# schematic.net
KiCad netlist of a schematic drawn in EasyEDA
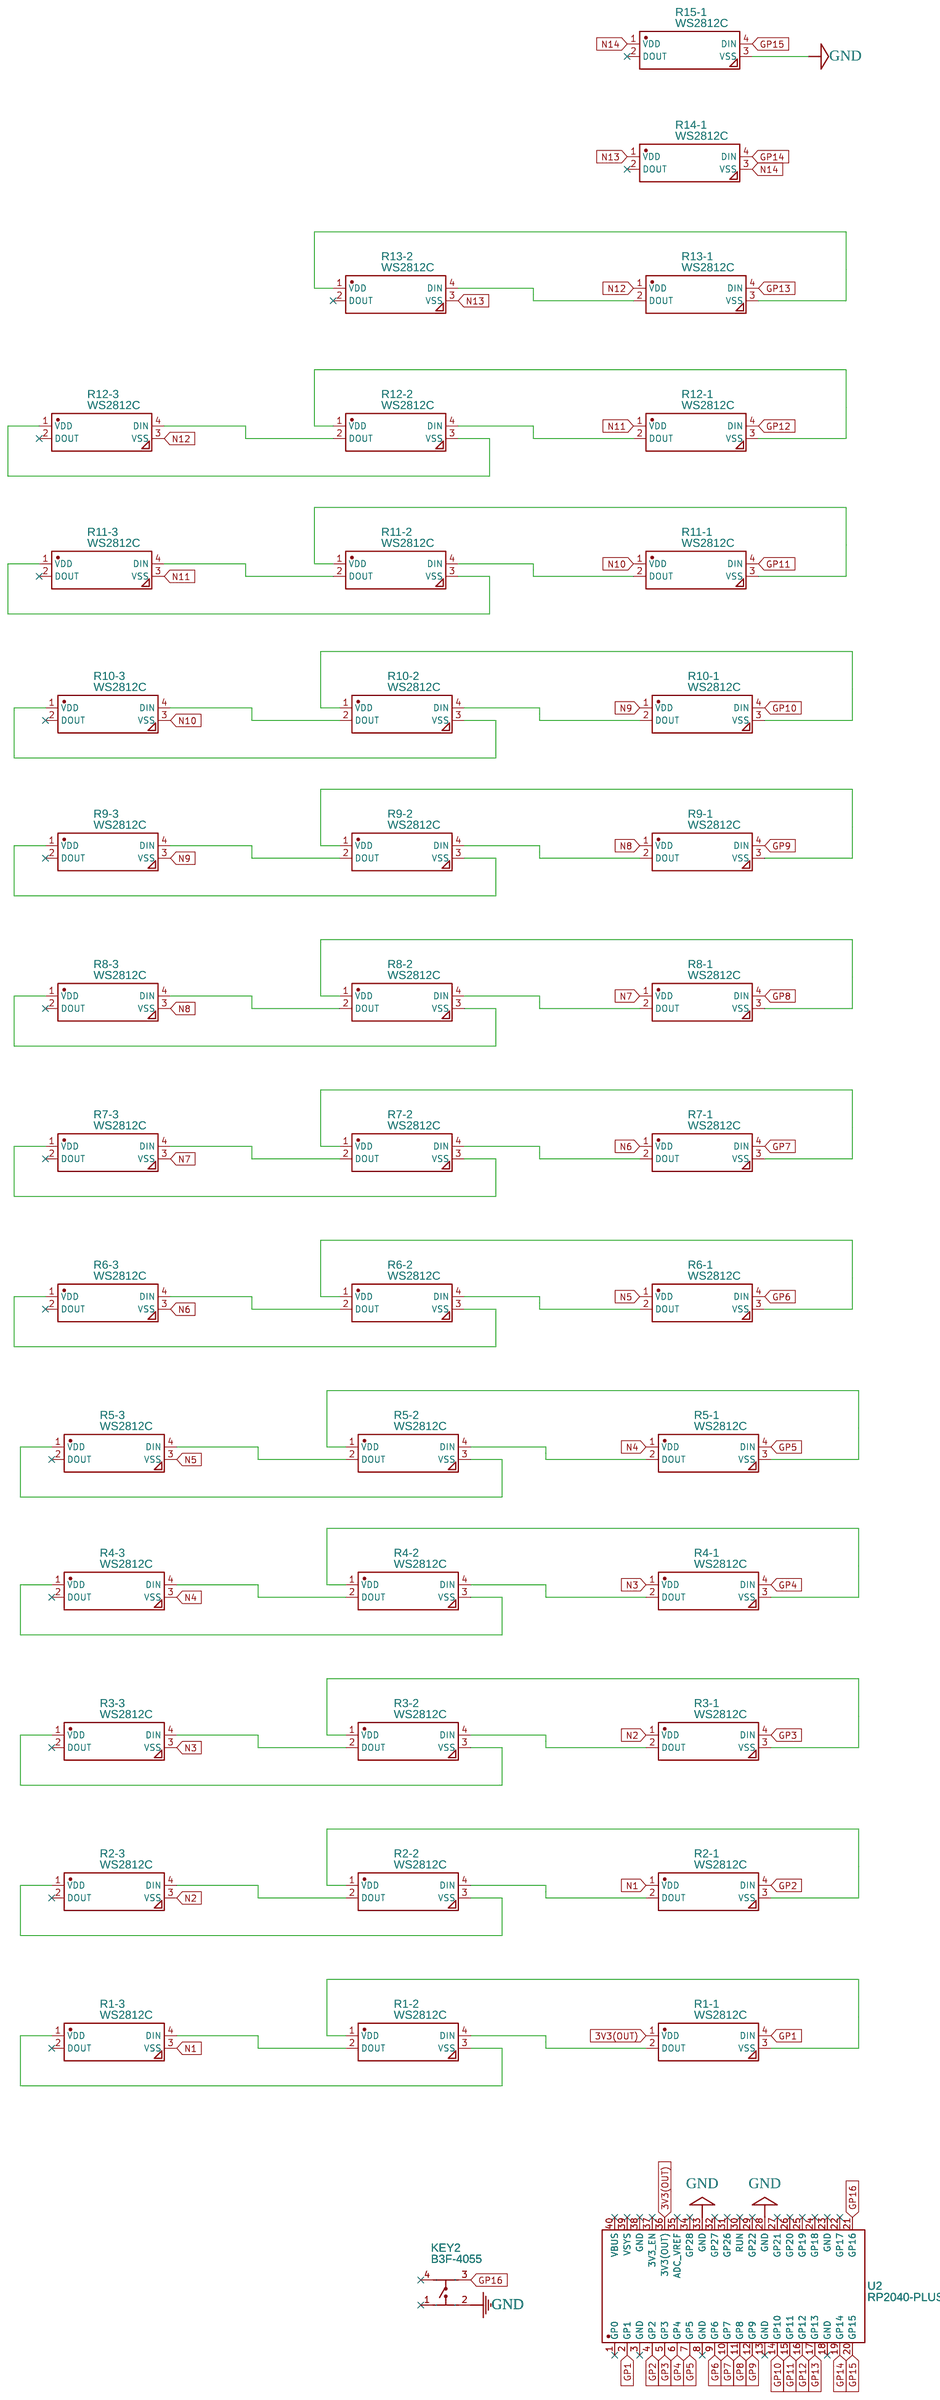
[diagram p0: Sheet_1]
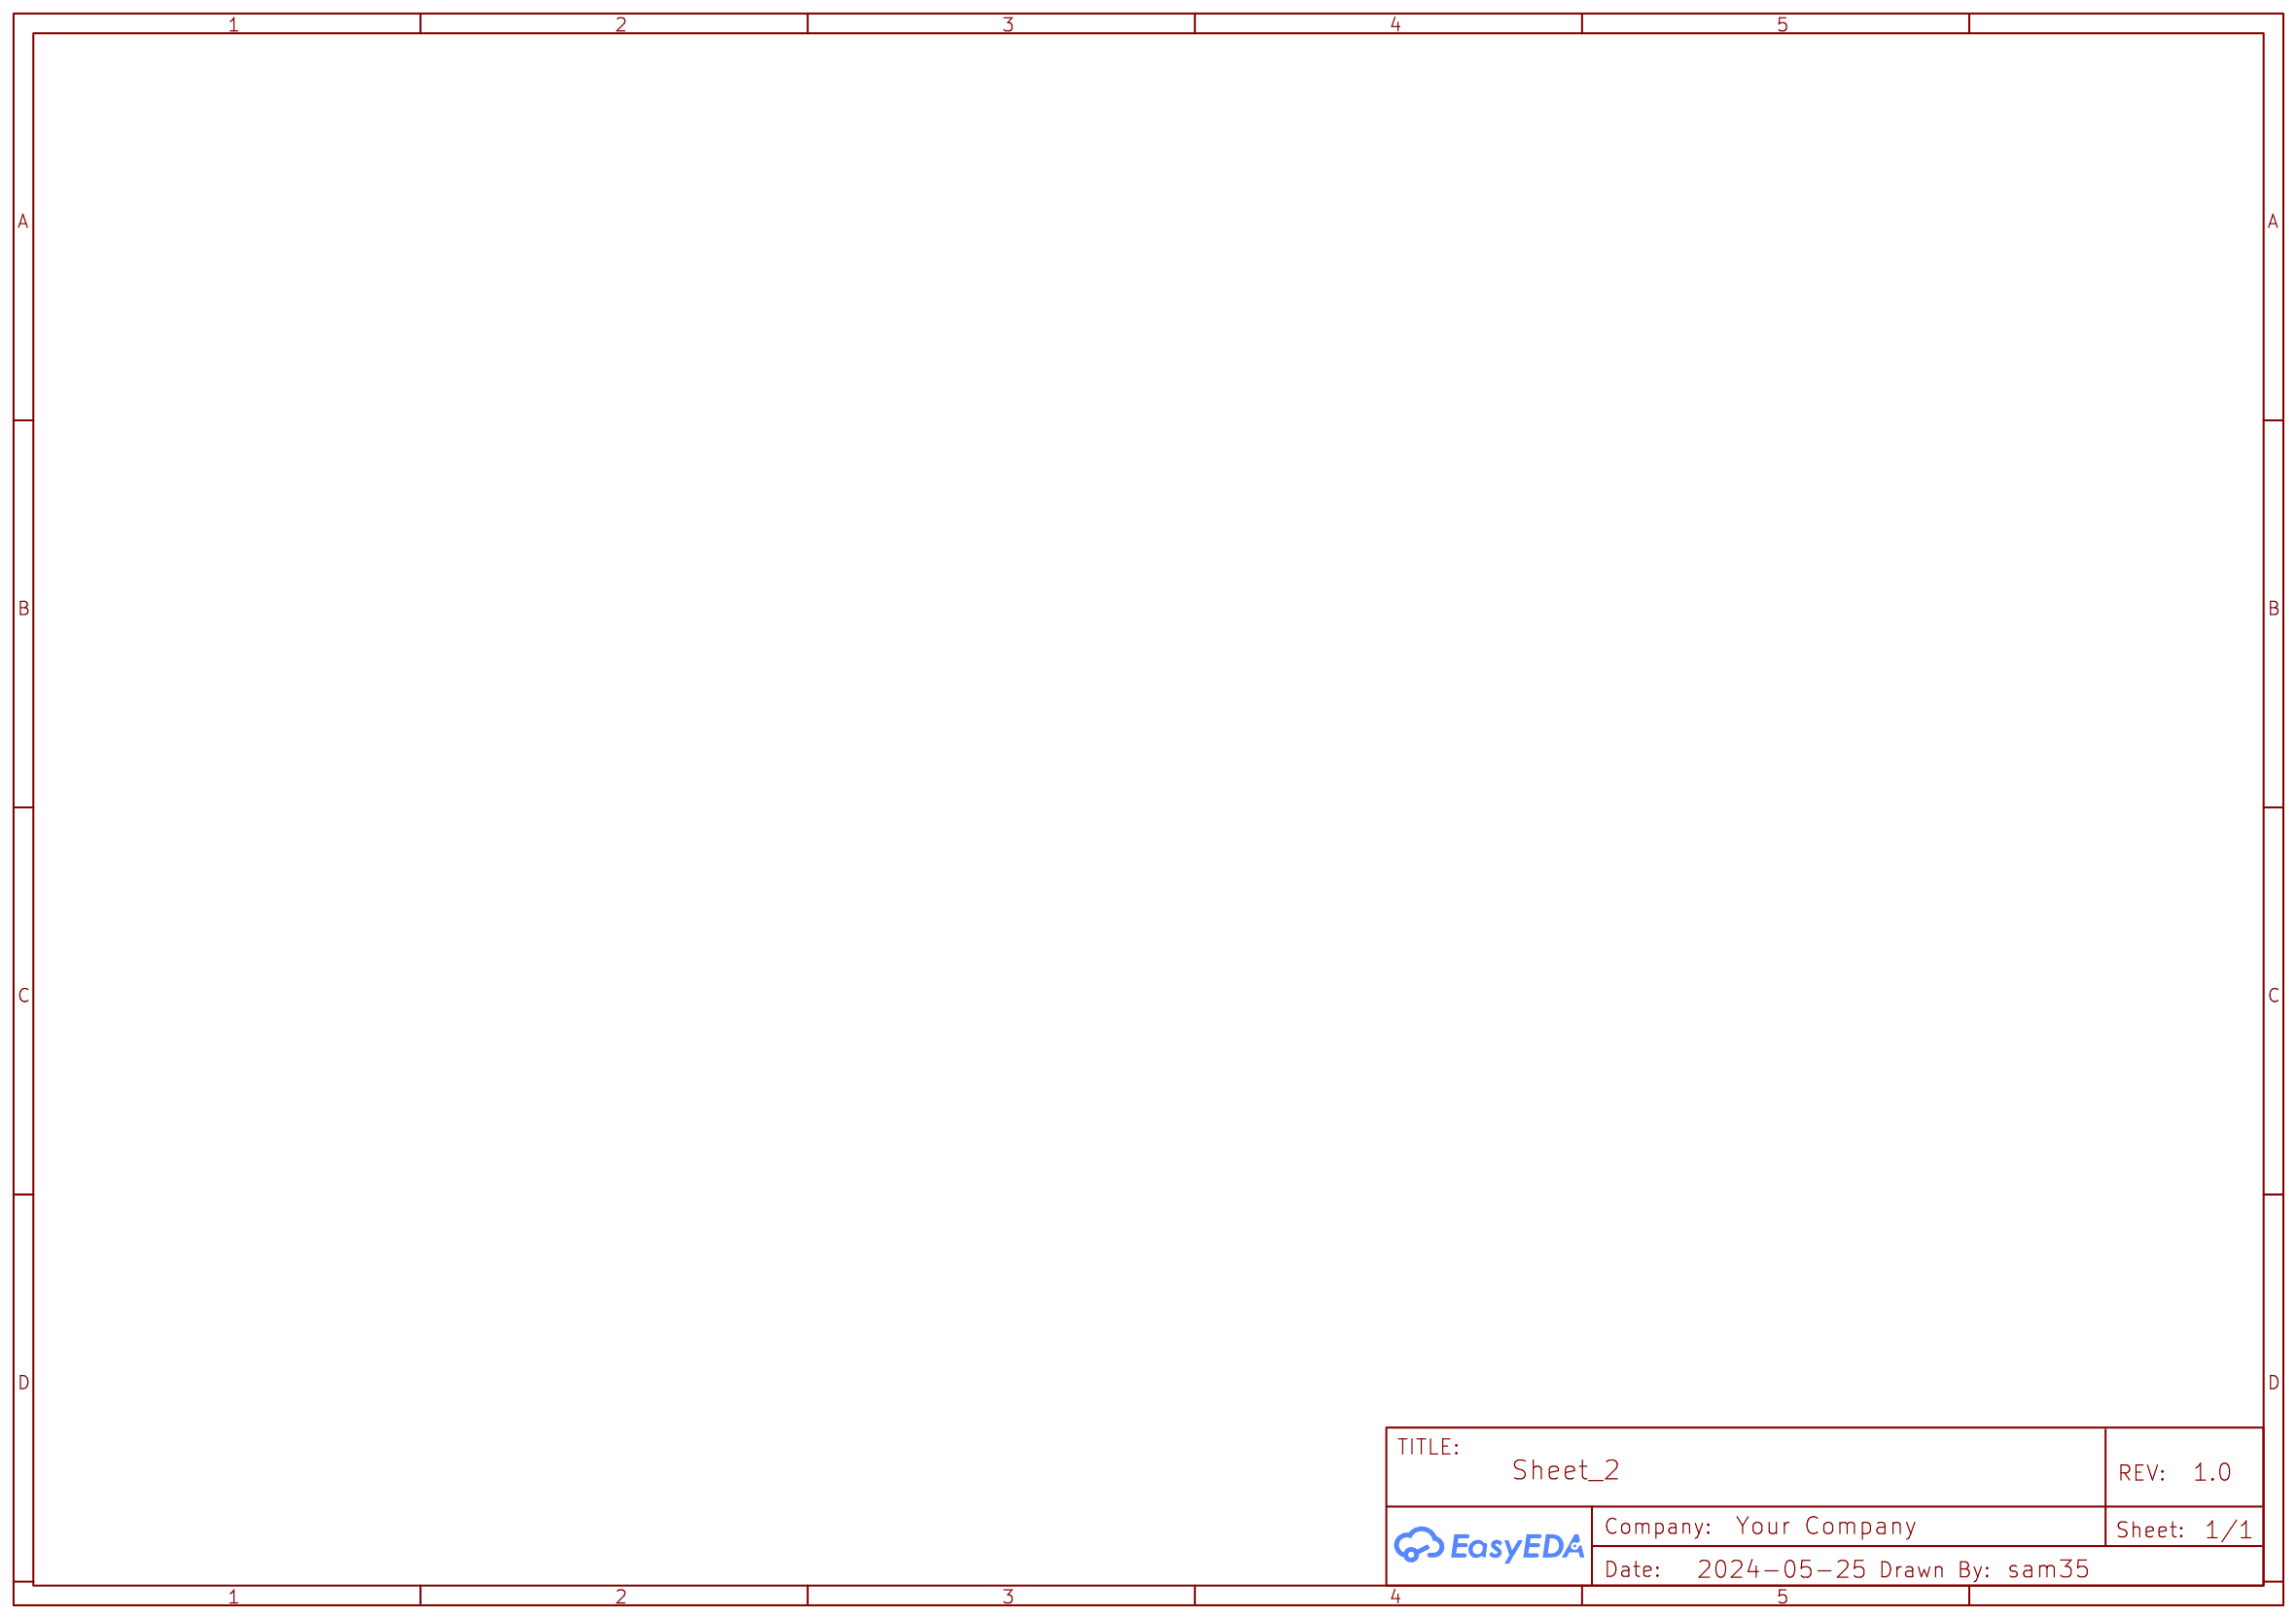
[diagram p1: Sheet_2]

(export (version "E")
  (design (tool "Eeschema 10.0.6"))
  (components
    (comp (ref "KEY2")
      (value "B3F-4055")
      (fields (field (name "Manufacturer") "OMRON(欧姆龙)"))
      (libsource (lib "") (part "B3F-4055"))
    )
    (comp (ref "R1-1")
      (value "WS2812C")
      (fields (field (name "Manufacturer") "worldsemi"))
      (libsource (lib "") (part "WS2812C_10"))
    )
    (comp (ref "R1-2")
      (value "WS2812C")
      (fields (field (name "Manufacturer") "worldsemi"))
      (libsource (lib "") (part "WS2812C_10"))
    )
    (comp (ref "R1-3")
      (value "WS2812C")
      (fields (field (name "Manufacturer") "worldsemi"))
      (libsource (lib "") (part "WS2812C_10"))
    )
    (comp (ref "R2-1")
      (value "WS2812C")
      (fields (field (name "Manufacturer") "worldsemi"))
      (libsource (lib "") (part "WS2812C"))
    )
    (comp (ref "R2-2")
      (value "WS2812C")
      (fields (field (name "Manufacturer") "worldsemi"))
      (libsource (lib "") (part "WS2812C"))
    )
    (comp (ref "R2-3")
      (value "WS2812C")
      (fields (field (name "Manufacturer") "worldsemi"))
      (libsource (lib "") (part "WS2812C"))
    )
    (comp (ref "R3-1")
      (value "WS2812C")
      (fields (field (name "Manufacturer") "worldsemi"))
      (libsource (lib "") (part "WS2812C_11"))
    )
    (comp (ref "R3-2")
      (value "WS2812C")
      (fields (field (name "Manufacturer") "worldsemi"))
      (libsource (lib "") (part "WS2812C_11"))
    )
    (comp (ref "R3-3")
      (value "WS2812C")
      (fields (field (name "Manufacturer") "worldsemi"))
      (libsource (lib "") (part "WS2812C_11"))
    )
    (comp (ref "R4-1")
      (value "WS2812C")
      (fields (field (name "Manufacturer") "worldsemi"))
      (libsource (lib "") (part "WS2812C_12"))
    )
    (comp (ref "R4-2")
      (value "WS2812C")
      (fields (field (name "Manufacturer") "worldsemi"))
      (libsource (lib "") (part "WS2812C_12"))
    )
    (comp (ref "R4-3")
      (value "WS2812C")
      (fields (field (name "Manufacturer") "worldsemi"))
      (libsource (lib "") (part "WS2812C_12"))
    )
    (comp (ref "R5-1")
      (value "WS2812C")
      (fields (field (name "Manufacturer") "worldsemi"))
      (libsource (lib "") (part "WS2812C_2"))
    )
    (comp (ref "R5-2")
      (value "WS2812C")
      (fields (field (name "Manufacturer") "worldsemi"))
      (libsource (lib "") (part "WS2812C_2"))
    )
    (comp (ref "R5-3")
      (value "WS2812C")
      (fields (field (name "Manufacturer") "worldsemi"))
      (libsource (lib "") (part "WS2812C_2"))
    )
    (comp (ref "R6-1")
      (value "WS2812C")
      (fields (field (name "Manufacturer") "worldsemi"))
      (libsource (lib "") (part "WS2812C_3"))
    )
    (comp (ref "R6-2")
      (value "WS2812C")
      (fields (field (name "Manufacturer") "worldsemi"))
      (libsource (lib "") (part "WS2812C_3"))
    )
    (comp (ref "R6-3")
      (value "WS2812C")
      (fields (field (name "Manufacturer") "worldsemi"))
      (libsource (lib "") (part "WS2812C_3"))
    )
    (comp (ref "R7-1")
      (value "WS2812C")
      (fields (field (name "Manufacturer") "worldsemi"))
      (libsource (lib "") (part "WS2812C_13"))
    )
    (comp (ref "R7-2")
      (value "WS2812C")
      (fields (field (name "Manufacturer") "worldsemi"))
      (libsource (lib "") (part "WS2812C_13"))
    )
    (comp (ref "R7-3")
      (value "WS2812C")
      (fields (field (name "Manufacturer") "worldsemi"))
      (libsource (lib "") (part "WS2812C_13"))
    )
    (comp (ref "R8-1")
      (value "WS2812C")
      (fields (field (name "Manufacturer") "worldsemi"))
      (libsource (lib "") (part "WS2812C_5"))
    )
    (comp (ref "R8-2")
      (value "WS2812C")
      (fields (field (name "Manufacturer") "worldsemi"))
      (libsource (lib "") (part "WS2812C_5"))
    )
    (comp (ref "R8-3")
      (value "WS2812C")
      (fields (field (name "Manufacturer") "worldsemi"))
      (libsource (lib "") (part "WS2812C_5"))
    )
    (comp (ref "R9-1")
      (value "WS2812C")
      (fields (field (name "Manufacturer") "worldsemi"))
      (libsource (lib "") (part "WS2812C_1"))
    )
    (comp (ref "R9-2")
      (value "WS2812C")
      (fields (field (name "Manufacturer") "worldsemi"))
      (libsource (lib "") (part "WS2812C_1"))
    )
    (comp (ref "R9-3")
      (value "WS2812C")
      (fields (field (name "Manufacturer") "worldsemi"))
      (libsource (lib "") (part "WS2812C_1"))
    )
    (comp (ref "R10-1")
      (value "WS2812C")
      (fields (field (name "Manufacturer") "worldsemi"))
      (libsource (lib "") (part "WS2812C_9"))
    )
    (comp (ref "R10-2")
      (value "WS2812C")
      (fields (field (name "Manufacturer") "worldsemi"))
      (libsource (lib "") (part "WS2812C_9"))
    )
    (comp (ref "R10-3")
      (value "WS2812C")
      (fields (field (name "Manufacturer") "worldsemi"))
      (libsource (lib "") (part "WS2812C_9"))
    )
    (comp (ref "R11-1")
      (value "WS2812C")
      (fields (field (name "Manufacturer") "worldsemi"))
      (libsource (lib "") (part "WS2812C_7"))
    )
    (comp (ref "R11-2")
      (value "WS2812C")
      (fields (field (name "Manufacturer") "worldsemi"))
      (libsource (lib "") (part "WS2812C_7"))
    )
    (comp (ref "R11-3")
      (value "WS2812C")
      (fields (field (name "Manufacturer") "worldsemi"))
      (libsource (lib "") (part "WS2812C_7"))
    )
    (comp (ref "R12-1")
      (value "WS2812C")
      (fields (field (name "Manufacturer") "worldsemi"))
      (libsource (lib "") (part "WS2812C_8"))
    )
    (comp (ref "R12-2")
      (value "WS2812C")
      (fields (field (name "Manufacturer") "worldsemi"))
      (libsource (lib "") (part "WS2812C_8"))
    )
    (comp (ref "R12-3")
      (value "WS2812C")
      (fields (field (name "Manufacturer") "worldsemi"))
      (libsource (lib "") (part "WS2812C_8"))
    )
    (comp (ref "R13-1")
      (value "WS2812C")
      (fields (field (name "Manufacturer") "worldsemi"))
      (libsource (lib "") (part "WS2812C_4"))
    )
    (comp (ref "R13-2")
      (value "WS2812C")
      (fields (field (name "Manufacturer") "worldsemi"))
      (libsource (lib "") (part "WS2812C_4"))
    )
    (comp (ref "R14-1")
      (value "WS2812C")
      (fields (field (name "Manufacturer") "worldsemi"))
      (libsource (lib "") (part "WS2812C_6"))
    )
    (comp (ref "R15-1")
      (value "WS2812C")
      (fields (field (name "Manufacturer") "worldsemi"))
      (libsource (lib "") (part "WS2812C_14"))
    )
    (comp (ref "U2")
      (value "RP2040-PLUS")
      (fields
        (field (name "Manufacturer Part") "RP2040-Plus")
        (field (name "Manufacturer") "Waveshare(微雪电子)")
      )
      (libsource (lib "") (part "RP2040-PLUS"))
    )
  )
  (nets
    (net (code "1") (name "3V3(OUT)") (class "Default")
      (node (ref "R1-1") (pin "1") (pinfunction "VDD_1") (pintype "unspecified"))
      (node (ref "U2") (pin "36") (pinfunction "3V3(OUT)_36") (pintype "unspecified"))
    )
    (net (code "2") (name "GND") (class "Default")
      (node (ref "KEY2") (pin "2") (pinfunction "2_2") (pintype "unspecified"))
      (node (ref "R15-1") (pin "3") (pinfunction "VSS_3") (pintype "unspecified"))
      (node (ref "U2") (pin "28") (pinfunction "GND_28") (pintype "unspecified"))
      (node (ref "U2") (pin "33") (pinfunction "GND_33") (pintype "unspecified"))
    )
    (net (code "3") (name "GP1") (class "Default")
      (node (ref "R1-1") (pin "4") (pinfunction "DIN_4") (pintype "unspecified"))
      (node (ref "U2") (pin "2") (pinfunction "GP1_2") (pintype "unspecified"))
    )
    (net (code "4") (name "GP2") (class "Default")
      (node (ref "R2-1") (pin "4") (pinfunction "DIN_4") (pintype "unspecified"))
      (node (ref "U2") (pin "4") (pinfunction "GP2_4") (pintype "unspecified"))
    )
    (net (code "5") (name "GP3") (class "Default")
      (node (ref "R3-1") (pin "4") (pinfunction "DIN_4") (pintype "unspecified"))
      (node (ref "U2") (pin "5") (pinfunction "GP3_5") (pintype "unspecified"))
    )
    (net (code "6") (name "GP4") (class "Default")
      (node (ref "R4-1") (pin "4") (pinfunction "DIN_4") (pintype "unspecified"))
      (node (ref "U2") (pin "6") (pinfunction "GP4_6") (pintype "unspecified"))
    )
    (net (code "7") (name "GP5") (class "Default")
      (node (ref "R5-1") (pin "4") (pinfunction "DIN_4") (pintype "unspecified"))
      (node (ref "U2") (pin "7") (pinfunction "GP5_7") (pintype "unspecified"))
    )
    (net (code "8") (name "GP6") (class "Default")
      (node (ref "R6-1") (pin "4") (pinfunction "DIN_4") (pintype "unspecified"))
      (node (ref "U2") (pin "9") (pinfunction "GP6_9") (pintype "unspecified"))
    )
    (net (code "9") (name "GP7") (class "Default")
      (node (ref "R7-1") (pin "4") (pinfunction "DIN_4") (pintype "unspecified"))
      (node (ref "U2") (pin "10") (pinfunction "GP7_10") (pintype "unspecified"))
    )
    (net (code "10") (name "GP8") (class "Default")
      (node (ref "R8-1") (pin "4") (pinfunction "DIN_4") (pintype "unspecified"))
      (node (ref "U2") (pin "11") (pinfunction "GP8_11") (pintype "unspecified"))
    )
    (net (code "11") (name "GP9") (class "Default")
      (node (ref "R9-1") (pin "4") (pinfunction "DIN_4") (pintype "unspecified"))
      (node (ref "U2") (pin "12") (pinfunction "GP9_12") (pintype "unspecified"))
    )
    (net (code "12") (name "GP10") (class "Default")
      (node (ref "R10-1") (pin "4") (pinfunction "DIN_4") (pintype "unspecified"))
      (node (ref "U2") (pin "14") (pinfunction "GP10_14") (pintype "unspecified"))
    )
    (net (code "13") (name "GP11") (class "Default")
      (node (ref "R11-1") (pin "4") (pinfunction "DIN_4") (pintype "unspecified"))
      (node (ref "U2") (pin "15") (pinfunction "GP11_15") (pintype "unspecified"))
    )
    (net (code "14") (name "GP12") (class "Default")
      (node (ref "R12-1") (pin "4") (pinfunction "DIN_4") (pintype "unspecified"))
      (node (ref "U2") (pin "16") (pinfunction "GP12_16") (pintype "unspecified"))
    )
    (net (code "15") (name "GP13") (class "Default")
      (node (ref "R13-1") (pin "4") (pinfunction "DIN_4") (pintype "unspecified"))
      (node (ref "U2") (pin "17") (pinfunction "GP13_17") (pintype "unspecified"))
    )
    (net (code "16") (name "GP14") (class "Default")
      (node (ref "R14-1") (pin "4") (pinfunction "DIN_4") (pintype "unspecified"))
      (node (ref "U2") (pin "19") (pinfunction "GP14_19") (pintype "unspecified"))
    )
    (net (code "17") (name "GP15") (class "Default")
      (node (ref "R15-1") (pin "4") (pinfunction "DIN_4") (pintype "unspecified"))
      (node (ref "U2") (pin "20") (pinfunction "GP15_20") (pintype "unspecified"))
    )
    (net (code "18") (name "GP16") (class "Default")
      (node (ref "KEY2") (pin "3") (pinfunction "3_3") (pintype "unspecified"))
      (node (ref "U2") (pin "21") (pinfunction "GP16_21") (pintype "unspecified"))
    )
    (net (code "19") (name "N1") (class "Default")
      (node (ref "R1-3") (pin "3") (pinfunction "VSS_3") (pintype "unspecified"))
      (node (ref "R2-1") (pin "1") (pinfunction "VDD_1") (pintype "unspecified"))
    )
    (net (code "20") (name "N2") (class "Default")
      (node (ref "R2-3") (pin "3") (pinfunction "VSS_3") (pintype "unspecified"))
      (node (ref "R3-1") (pin "1") (pinfunction "VDD_1") (pintype "unspecified"))
    )
    (net (code "21") (name "N3") (class "Default")
      (node (ref "R3-3") (pin "3") (pinfunction "VSS_3") (pintype "unspecified"))
      (node (ref "R4-1") (pin "1") (pinfunction "VDD_1") (pintype "unspecified"))
    )
    (net (code "22") (name "N4") (class "Default")
      (node (ref "R4-3") (pin "3") (pinfunction "VSS_3") (pintype "unspecified"))
      (node (ref "R5-1") (pin "1") (pinfunction "VDD_1") (pintype "unspecified"))
    )
    (net (code "23") (name "N5") (class "Default")
      (node (ref "R5-3") (pin "3") (pinfunction "VSS_3") (pintype "unspecified"))
      (node (ref "R6-1") (pin "1") (pinfunction "VDD_1") (pintype "unspecified"))
    )
    (net (code "24") (name "N6") (class "Default")
      (node (ref "R6-3") (pin "3") (pinfunction "VSS_3") (pintype "unspecified"))
      (node (ref "R7-1") (pin "1") (pinfunction "VDD_1") (pintype "unspecified"))
    )
    (net (code "25") (name "N7") (class "Default")
      (node (ref "R7-3") (pin "3") (pinfunction "VSS_3") (pintype "unspecified"))
      (node (ref "R8-1") (pin "1") (pinfunction "VDD_1") (pintype "unspecified"))
    )
    (net (code "26") (name "N8") (class "Default")
      (node (ref "R8-3") (pin "3") (pinfunction "VSS_3") (pintype "unspecified"))
      (node (ref "R9-1") (pin "1") (pinfunction "VDD_1") (pintype "unspecified"))
    )
    (net (code "27") (name "N9") (class "Default")
      (node (ref "R10-1") (pin "1") (pinfunction "VDD_1") (pintype "unspecified"))
      (node (ref "R9-3") (pin "3") (pinfunction "VSS_3") (pintype "unspecified"))
    )
    (net (code "28") (name "N10") (class "Default")
      (node (ref "R10-3") (pin "3") (pinfunction "VSS_3") (pintype "unspecified"))
      (node (ref "R11-1") (pin "1") (pinfunction "VDD_1") (pintype "unspecified"))
    )
    (net (code "29") (name "N11") (class "Default")
      (node (ref "R11-3") (pin "3") (pinfunction "VSS_3") (pintype "unspecified"))
      (node (ref "R12-1") (pin "1") (pinfunction "VDD_1") (pintype "unspecified"))
    )
    (net (code "30") (name "N12") (class "Default")
      (node (ref "R12-3") (pin "3") (pinfunction "VSS_3") (pintype "unspecified"))
      (node (ref "R13-1") (pin "1") (pinfunction "VDD_1") (pintype "unspecified"))
    )
    (net (code "31") (name "N13") (class "Default")
      (node (ref "R13-2") (pin "3") (pinfunction "VSS_3") (pintype "unspecified"))
      (node (ref "R14-1") (pin "1") (pinfunction "VDD_1") (pintype "unspecified"))
    )
    (net (code "32") (name "N14") (class "Default")
      (node (ref "R14-1") (pin "3") (pinfunction "VSS_3") (pintype "unspecified"))
      (node (ref "R15-1") (pin "1") (pinfunction "VDD_1") (pintype "unspecified"))
    )
    (net (code "33") (name "Net-(R1-1-DOUT)") (class "Default")
      (node (ref "R1-1") (pin "2") (pinfunction "DOUT_2") (pintype "unspecified"))
      (node (ref "R1-2") (pin "4") (pinfunction "DIN_4") (pintype "unspecified"))
    )
    (net (code "34") (name "Net-(R1-1-VSS)") (class "Default")
      (node (ref "R1-1") (pin "3") (pinfunction "VSS_3") (pintype "unspecified"))
      (node (ref "R1-2") (pin "1") (pinfunction "VDD_1") (pintype "unspecified"))
    )
    (net (code "35") (name "Net-(R1-2-DOUT)") (class "Default")
      (node (ref "R1-2") (pin "2") (pinfunction "DOUT_2") (pintype "unspecified"))
      (node (ref "R1-3") (pin "4") (pinfunction "DIN_4") (pintype "unspecified"))
    )
    (net (code "36") (name "Net-(R1-2-VSS)") (class "Default")
      (node (ref "R1-2") (pin "3") (pinfunction "VSS_3") (pintype "unspecified"))
      (node (ref "R1-3") (pin "1") (pinfunction "VDD_1") (pintype "unspecified"))
    )
    (net (code "37") (name "Net-(R2-1-DOUT)") (class "Default")
      (node (ref "R2-1") (pin "2") (pinfunction "DOUT_2") (pintype "unspecified"))
      (node (ref "R2-2") (pin "4") (pinfunction "DIN_4") (pintype "unspecified"))
    )
    (net (code "38") (name "Net-(R2-1-VSS)") (class "Default")
      (node (ref "R2-1") (pin "3") (pinfunction "VSS_3") (pintype "unspecified"))
      (node (ref "R2-2") (pin "1") (pinfunction "VDD_1") (pintype "unspecified"))
    )
    (net (code "39") (name "Net-(R2-2-DOUT)") (class "Default")
      (node (ref "R2-2") (pin "2") (pinfunction "DOUT_2") (pintype "unspecified"))
      (node (ref "R2-3") (pin "4") (pinfunction "DIN_4") (pintype "unspecified"))
    )
    (net (code "40") (name "Net-(R2-2-VSS)") (class "Default")
      (node (ref "R2-2") (pin "3") (pinfunction "VSS_3") (pintype "unspecified"))
      (node (ref "R2-3") (pin "1") (pinfunction "VDD_1") (pintype "unspecified"))
    )
    (net (code "41") (name "Net-(R3-1-DOUT)") (class "Default")
      (node (ref "R3-1") (pin "2") (pinfunction "DOUT_2") (pintype "unspecified"))
      (node (ref "R3-2") (pin "4") (pinfunction "DIN_4") (pintype "unspecified"))
    )
    (net (code "42") (name "Net-(R3-1-VSS)") (class "Default")
      (node (ref "R3-1") (pin "3") (pinfunction "VSS_3") (pintype "unspecified"))
      (node (ref "R3-2") (pin "1") (pinfunction "VDD_1") (pintype "unspecified"))
    )
    (net (code "43") (name "Net-(R3-2-DOUT)") (class "Default")
      (node (ref "R3-2") (pin "2") (pinfunction "DOUT_2") (pintype "unspecified"))
      (node (ref "R3-3") (pin "4") (pinfunction "DIN_4") (pintype "unspecified"))
    )
    (net (code "44") (name "Net-(R3-2-VSS)") (class "Default")
      (node (ref "R3-2") (pin "3") (pinfunction "VSS_3") (pintype "unspecified"))
      (node (ref "R3-3") (pin "1") (pinfunction "VDD_1") (pintype "unspecified"))
    )
    (net (code "45") (name "Net-(R4-1-DOUT)") (class "Default")
      (node (ref "R4-1") (pin "2") (pinfunction "DOUT_2") (pintype "unspecified"))
      (node (ref "R4-2") (pin "4") (pinfunction "DIN_4") (pintype "unspecified"))
    )
    (net (code "46") (name "Net-(R4-1-VSS)") (class "Default")
      (node (ref "R4-1") (pin "3") (pinfunction "VSS_3") (pintype "unspecified"))
      (node (ref "R4-2") (pin "1") (pinfunction "VDD_1") (pintype "unspecified"))
    )
    (net (code "47") (name "Net-(R4-2-DOUT)") (class "Default")
      (node (ref "R4-2") (pin "2") (pinfunction "DOUT_2") (pintype "unspecified"))
      (node (ref "R4-3") (pin "4") (pinfunction "DIN_4") (pintype "unspecified"))
    )
    (net (code "48") (name "Net-(R4-2-VSS)") (class "Default")
      (node (ref "R4-2") (pin "3") (pinfunction "VSS_3") (pintype "unspecified"))
      (node (ref "R4-3") (pin "1") (pinfunction "VDD_1") (pintype "unspecified"))
    )
    (net (code "49") (name "Net-(R5-1-DOUT)") (class "Default")
      (node (ref "R5-1") (pin "2") (pinfunction "DOUT_2") (pintype "unspecified"))
      (node (ref "R5-2") (pin "4") (pinfunction "DIN_4") (pintype "unspecified"))
    )
    (net (code "50") (name "Net-(R5-1-VSS)") (class "Default")
      (node (ref "R5-1") (pin "3") (pinfunction "VSS_3") (pintype "unspecified"))
      (node (ref "R5-2") (pin "1") (pinfunction "VDD_1") (pintype "unspecified"))
    )
    (net (code "51") (name "Net-(R5-2-DOUT)") (class "Default")
      (node (ref "R5-2") (pin "2") (pinfunction "DOUT_2") (pintype "unspecified"))
      (node (ref "R5-3") (pin "4") (pinfunction "DIN_4") (pintype "unspecified"))
    )
    (net (code "52") (name "Net-(R5-2-VSS)") (class "Default")
      (node (ref "R5-2") (pin "3") (pinfunction "VSS_3") (pintype "unspecified"))
      (node (ref "R5-3") (pin "1") (pinfunction "VDD_1") (pintype "unspecified"))
    )
    (net (code "53") (name "Net-(R6-1-DOUT)") (class "Default")
      (node (ref "R6-1") (pin "2") (pinfunction "DOUT_2") (pintype "unspecified"))
      (node (ref "R6-2") (pin "4") (pinfunction "DIN_4") (pintype "unspecified"))
    )
    (net (code "54") (name "Net-(R6-1-VSS)") (class "Default")
      (node (ref "R6-1") (pin "3") (pinfunction "VSS_3") (pintype "unspecified"))
      (node (ref "R6-2") (pin "1") (pinfunction "VDD_1") (pintype "unspecified"))
    )
    (net (code "55") (name "Net-(R6-2-DOUT)") (class "Default")
      (node (ref "R6-2") (pin "2") (pinfunction "DOUT_2") (pintype "unspecified"))
      (node (ref "R6-3") (pin "4") (pinfunction "DIN_4") (pintype "unspecified"))
    )
    (net (code "56") (name "Net-(R6-2-VSS)") (class "Default")
      (node (ref "R6-2") (pin "3") (pinfunction "VSS_3") (pintype "unspecified"))
      (node (ref "R6-3") (pin "1") (pinfunction "VDD_1") (pintype "unspecified"))
    )
    (net (code "57") (name "Net-(R7-1-DOUT)") (class "Default")
      (node (ref "R7-1") (pin "2") (pinfunction "DOUT_2") (pintype "unspecified"))
      (node (ref "R7-2") (pin "4") (pinfunction "DIN_4") (pintype "unspecified"))
    )
    (net (code "58") (name "Net-(R7-1-VSS)") (class "Default")
      (node (ref "R7-1") (pin "3") (pinfunction "VSS_3") (pintype "unspecified"))
      (node (ref "R7-2") (pin "1") (pinfunction "VDD_1") (pintype "unspecified"))
    )
    (net (code "59") (name "Net-(R7-2-DOUT)") (class "Default")
      (node (ref "R7-2") (pin "2") (pinfunction "DOUT_2") (pintype "unspecified"))
      (node (ref "R7-3") (pin "4") (pinfunction "DIN_4") (pintype "unspecified"))
    )
    (net (code "60") (name "Net-(R7-2-VSS)") (class "Default")
      (node (ref "R7-2") (pin "3") (pinfunction "VSS_3") (pintype "unspecified"))
      (node (ref "R7-3") (pin "1") (pinfunction "VDD_1") (pintype "unspecified"))
    )
    (net (code "61") (name "Net-(R8-1-DOUT)") (class "Default")
      (node (ref "R8-1") (pin "2") (pinfunction "DOUT_2") (pintype "unspecified"))
      (node (ref "R8-2") (pin "4") (pinfunction "DIN_4") (pintype "unspecified"))
    )
    (net (code "62") (name "Net-(R8-1-VSS)") (class "Default")
      (node (ref "R8-1") (pin "3") (pinfunction "VSS_3") (pintype "unspecified"))
      (node (ref "R8-2") (pin "1") (pinfunction "VDD_1") (pintype "unspecified"))
    )
    (net (code "63") (name "Net-(R8-2-DOUT)") (class "Default")
      (node (ref "R8-2") (pin "2") (pinfunction "DOUT_2") (pintype "unspecified"))
      (node (ref "R8-3") (pin "4") (pinfunction "DIN_4") (pintype "unspecified"))
    )
    (net (code "64") (name "Net-(R8-2-VSS)") (class "Default")
      (node (ref "R8-2") (pin "3") (pinfunction "VSS_3") (pintype "unspecified"))
      (node (ref "R8-3") (pin "1") (pinfunction "VDD_1") (pintype "unspecified"))
    )
    (net (code "65") (name "Net-(R9-1-DOUT)") (class "Default")
      (node (ref "R9-1") (pin "2") (pinfunction "DOUT_2") (pintype "unspecified"))
      (node (ref "R9-2") (pin "4") (pinfunction "DIN_4") (pintype "unspecified"))
    )
    (net (code "66") (name "Net-(R9-1-VSS)") (class "Default")
      (node (ref "R9-1") (pin "3") (pinfunction "VSS_3") (pintype "unspecified"))
      (node (ref "R9-2") (pin "1") (pinfunction "VDD_1") (pintype "unspecified"))
    )
    (net (code "67") (name "Net-(R9-2-DOUT)") (class "Default")
      (node (ref "R9-2") (pin "2") (pinfunction "DOUT_2") (pintype "unspecified"))
      (node (ref "R9-3") (pin "4") (pinfunction "DIN_4") (pintype "unspecified"))
    )
    (net (code "68") (name "Net-(R9-2-VSS)") (class "Default")
      (node (ref "R9-2") (pin "3") (pinfunction "VSS_3") (pintype "unspecified"))
      (node (ref "R9-3") (pin "1") (pinfunction "VDD_1") (pintype "unspecified"))
    )
    (net (code "69") (name "Net-(R10-1-DOUT)") (class "Default")
      (node (ref "R10-1") (pin "2") (pinfunction "DOUT_2") (pintype "unspecified"))
      (node (ref "R10-2") (pin "4") (pinfunction "DIN_4") (pintype "unspecified"))
    )
    (net (code "70") (name "Net-(R10-1-VSS)") (class "Default")
      (node (ref "R10-1") (pin "3") (pinfunction "VSS_3") (pintype "unspecified"))
      (node (ref "R10-2") (pin "1") (pinfunction "VDD_1") (pintype "unspecified"))
    )
    (net (code "71") (name "Net-(R10-2-DOUT)") (class "Default")
      (node (ref "R10-2") (pin "2") (pinfunction "DOUT_2") (pintype "unspecified"))
      (node (ref "R10-3") (pin "4") (pinfunction "DIN_4") (pintype "unspecified"))
    )
    (net (code "72") (name "Net-(R10-2-VSS)") (class "Default")
      (node (ref "R10-2") (pin "3") (pinfunction "VSS_3") (pintype "unspecified"))
      (node (ref "R10-3") (pin "1") (pinfunction "VDD_1") (pintype "unspecified"))
    )
    (net (code "73") (name "Net-(R11-1-DOUT)") (class "Default")
      (node (ref "R11-1") (pin "2") (pinfunction "DOUT_2") (pintype "unspecified"))
      (node (ref "R11-2") (pin "4") (pinfunction "DIN_4") (pintype "unspecified"))
    )
    (net (code "74") (name "Net-(R11-1-VSS)") (class "Default")
      (node (ref "R11-1") (pin "3") (pinfunction "VSS_3") (pintype "unspecified"))
      (node (ref "R11-2") (pin "1") (pinfunction "VDD_1") (pintype "unspecified"))
    )
    (net (code "75") (name "Net-(R11-2-DOUT)") (class "Default")
      (node (ref "R11-2") (pin "2") (pinfunction "DOUT_2") (pintype "unspecified"))
      (node (ref "R11-3") (pin "4") (pinfunction "DIN_4") (pintype "unspecified"))
    )
    (net (code "76") (name "Net-(R11-2-VSS)") (class "Default")
      (node (ref "R11-2") (pin "3") (pinfunction "VSS_3") (pintype "unspecified"))
      (node (ref "R11-3") (pin "1") (pinfunction "VDD_1") (pintype "unspecified"))
    )
    (net (code "77") (name "Net-(R12-1-DOUT)") (class "Default")
      (node (ref "R12-1") (pin "2") (pinfunction "DOUT_2") (pintype "unspecified"))
      (node (ref "R12-2") (pin "4") (pinfunction "DIN_4") (pintype "unspecified"))
    )
    (net (code "78") (name "Net-(R12-1-VSS)") (class "Default")
      (node (ref "R12-1") (pin "3") (pinfunction "VSS_3") (pintype "unspecified"))
      (node (ref "R12-2") (pin "1") (pinfunction "VDD_1") (pintype "unspecified"))
    )
    (net (code "79") (name "Net-(R12-2-DOUT)") (class "Default")
      (node (ref "R12-2") (pin "2") (pinfunction "DOUT_2") (pintype "unspecified"))
      (node (ref "R12-3") (pin "4") (pinfunction "DIN_4") (pintype "unspecified"))
    )
    (net (code "80") (name "Net-(R12-2-VSS)") (class "Default")
      (node (ref "R12-2") (pin "3") (pinfunction "VSS_3") (pintype "unspecified"))
      (node (ref "R12-3") (pin "1") (pinfunction "VDD_1") (pintype "unspecified"))
    )
    (net (code "81") (name "Net-(R13-1-DOUT)") (class "Default")
      (node (ref "R13-1") (pin "2") (pinfunction "DOUT_2") (pintype "unspecified"))
      (node (ref "R13-2") (pin "4") (pinfunction "DIN_4") (pintype "unspecified"))
    )
    (net (code "82") (name "Net-(R13-1-VSS)") (class "Default")
      (node (ref "R13-1") (pin "3") (pinfunction "VSS_3") (pintype "unspecified"))
      (node (ref "R13-2") (pin "1") (pinfunction "VDD_1") (pintype "unspecified"))
    )
    (net (code "83") (name "unconnected-(KEY2-Pad1)") (class "Default")
      (node (ref "KEY2") (pin "1") (pinfunction "1_1") (pintype "unspecified+no_connect"))
    )
    (net (code "84") (name "unconnected-(KEY2-Pad4)") (class "Default")
      (node (ref "KEY2") (pin "4") (pinfunction "4_4") (pintype "unspecified+no_connect"))
    )
    (net (code "85") (name "unconnected-(R1-3-DOUT-Pad2)") (class "Default")
      (node (ref "R1-3") (pin "2") (pinfunction "DOUT_2") (pintype "unspecified+no_connect"))
    )
    (net (code "86") (name "unconnected-(R2-3-DOUT-Pad2)") (class "Default")
      (node (ref "R2-3") (pin "2") (pinfunction "DOUT_2") (pintype "unspecified+no_connect"))
    )
    (net (code "87") (name "unconnected-(R3-3-DOUT-Pad2)") (class "Default")
      (node (ref "R3-3") (pin "2") (pinfunction "DOUT_2") (pintype "unspecified+no_connect"))
    )
    (net (code "88") (name "unconnected-(R4-3-DOUT-Pad2)") (class "Default")
      (node (ref "R4-3") (pin "2") (pinfunction "DOUT_2") (pintype "unspecified+no_connect"))
    )
    (net (code "89") (name "unconnected-(R5-3-DOUT-Pad2)") (class "Default")
      (node (ref "R5-3") (pin "2") (pinfunction "DOUT_2") (pintype "unspecified+no_connect"))
    )
    (net (code "90") (name "unconnected-(R6-3-DOUT-Pad2)") (class "Default")
      (node (ref "R6-3") (pin "2") (pinfunction "DOUT_2") (pintype "unspecified+no_connect"))
    )
    (net (code "91") (name "unconnected-(R7-3-DOUT-Pad2)") (class "Default")
      (node (ref "R7-3") (pin "2") (pinfunction "DOUT_2") (pintype "unspecified+no_connect"))
    )
    (net (code "92") (name "unconnected-(R8-3-DOUT-Pad2)") (class "Default")
      (node (ref "R8-3") (pin "2") (pinfunction "DOUT_2") (pintype "unspecified+no_connect"))
    )
    (net (code "93") (name "unconnected-(R9-3-DOUT-Pad2)") (class "Default")
      (node (ref "R9-3") (pin "2") (pinfunction "DOUT_2") (pintype "unspecified+no_connect"))
    )
    (net (code "94") (name "unconnected-(R10-3-DOUT-Pad2)") (class "Default")
      (node (ref "R10-3") (pin "2") (pinfunction "DOUT_2") (pintype "unspecified+no_connect"))
    )
    (net (code "95") (name "unconnected-(R11-3-DOUT-Pad2)") (class "Default")
      (node (ref "R11-3") (pin "2") (pinfunction "DOUT_2") (pintype "unspecified+no_connect"))
    )
    (net (code "96") (name "unconnected-(R12-3-DOUT-Pad2)") (class "Default")
      (node (ref "R12-3") (pin "2") (pinfunction "DOUT_2") (pintype "unspecified+no_connect"))
    )
    (net (code "97") (name "unconnected-(R13-2-DOUT-Pad2)") (class "Default")
      (node (ref "R13-2") (pin "2") (pinfunction "DOUT_2") (pintype "unspecified+no_connect"))
    )
    (net (code "98") (name "unconnected-(R14-1-DOUT-Pad2)") (class "Default")
      (node (ref "R14-1") (pin "2") (pinfunction "DOUT_2") (pintype "unspecified+no_connect"))
    )
    (net (code "99") (name "unconnected-(R15-1-DOUT-Pad2)") (class "Default")
      (node (ref "R15-1") (pin "2") (pinfunction "DOUT_2") (pintype "unspecified+no_connect"))
    )
    (net (code "100") (name "unconnected-(U2-3V3_EN-Pad37)") (class "Default")
      (node (ref "U2") (pin "37") (pinfunction "3V3_EN_37") (pintype "unspecified+no_connect"))
    )
    (net (code "101") (name "unconnected-(U2-ADC_VREF-Pad35)") (class "Default")
      (node (ref "U2") (pin "35") (pinfunction "ADC_VREF_35") (pintype "unspecified+no_connect"))
    )
    (net (code "102") (name "unconnected-(U2-GND-Pad3)") (class "Default")
      (node (ref "U2") (pin "3") (pinfunction "GND_3") (pintype "unspecified+no_connect"))
    )
    (net (code "103") (name "unconnected-(U2-GND-Pad8)") (class "Default")
      (node (ref "U2") (pin "8") (pinfunction "GND_8") (pintype "unspecified+no_connect"))
    )
    (net (code "104") (name "unconnected-(U2-GND-Pad13)") (class "Default")
      (node (ref "U2") (pin "13") (pinfunction "GND_13") (pintype "unspecified+no_connect"))
    )
    (net (code "105") (name "unconnected-(U2-GND-Pad18)") (class "Default")
      (node (ref "U2") (pin "18") (pinfunction "GND_18") (pintype "unspecified+no_connect"))
    )
    (net (code "106") (name "unconnected-(U2-GND-Pad23)") (class "Default")
      (node (ref "U2") (pin "23") (pinfunction "GND_23") (pintype "unspecified+no_connect"))
    )
    (net (code "107") (name "unconnected-(U2-GND-Pad38)") (class "Default")
      (node (ref "U2") (pin "38") (pinfunction "GND_38") (pintype "unspecified+no_connect"))
    )
    (net (code "108") (name "unconnected-(U2-GP0-Pad1)") (class "Default")
      (node (ref "U2") (pin "1") (pinfunction "GP0_1") (pintype "unspecified+no_connect"))
    )
    (net (code "109") (name "unconnected-(U2-GP17-Pad22)") (class "Default")
      (node (ref "U2") (pin "22") (pinfunction "GP17_22") (pintype "unspecified+no_connect"))
    )
    (net (code "110") (name "unconnected-(U2-GP18-Pad24)") (class "Default")
      (node (ref "U2") (pin "24") (pinfunction "GP18_24") (pintype "unspecified+no_connect"))
    )
    (net (code "111") (name "unconnected-(U2-GP19-Pad25)") (class "Default")
      (node (ref "U2") (pin "25") (pinfunction "GP19_25") (pintype "unspecified+no_connect"))
    )
    (net (code "112") (name "unconnected-(U2-GP20-Pad26)") (class "Default")
      (node (ref "U2") (pin "26") (pinfunction "GP20_26") (pintype "unspecified+no_connect"))
    )
    (net (code "113") (name "unconnected-(U2-GP21-Pad27)") (class "Default")
      (node (ref "U2") (pin "27") (pinfunction "GP21_27") (pintype "unspecified+no_connect"))
    )
    (net (code "114") (name "unconnected-(U2-GP22-Pad29)") (class "Default")
      (node (ref "U2") (pin "29") (pinfunction "GP22_29") (pintype "unspecified+no_connect"))
    )
    (net (code "115") (name "unconnected-(U2-GP26-Pad31)") (class "Default")
      (node (ref "U2") (pin "31") (pinfunction "GP26_31") (pintype "unspecified+no_connect"))
    )
    (net (code "116") (name "unconnected-(U2-GP27-Pad32)") (class "Default")
      (node (ref "U2") (pin "32") (pinfunction "GP27_32") (pintype "unspecified+no_connect"))
    )
    (net (code "117") (name "unconnected-(U2-GP28-Pad34)") (class "Default")
      (node (ref "U2") (pin "34") (pinfunction "GP28_34") (pintype "unspecified+no_connect"))
    )
    (net (code "118") (name "unconnected-(U2-RUN-Pad30)") (class "Default")
      (node (ref "U2") (pin "30") (pinfunction "RUN_30") (pintype "unspecified+no_connect"))
    )
    (net (code "119") (name "unconnected-(U2-VBUS-Pad40)") (class "Default")
      (node (ref "U2") (pin "40") (pinfunction "VBUS_40") (pintype "unspecified+no_connect"))
    )
    (net (code "120") (name "unconnected-(U2-VSYS-Pad39)") (class "Default")
      (node (ref "U2") (pin "39") (pinfunction "VSYS_39") (pintype "unspecified+no_connect"))
    )
  )
)
